# LedTaster_4TE_3_54.net
KiCad netlist of a schematic drawn in EAGLE
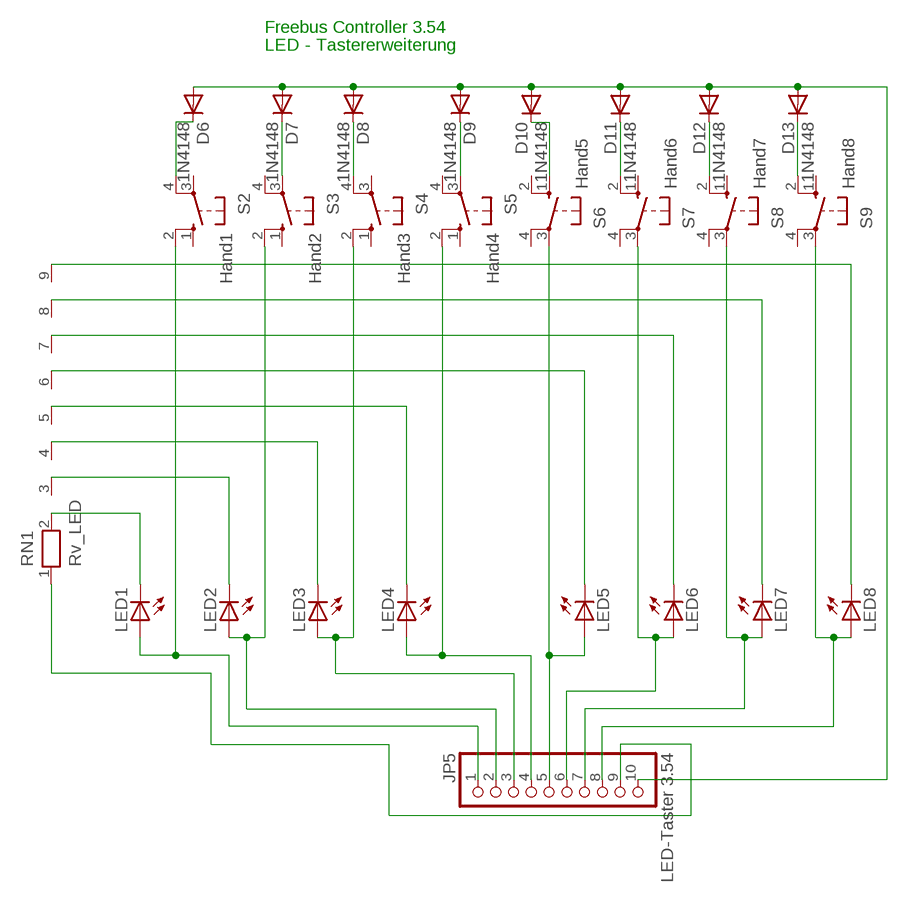
[diagram p0: schematic, sheet 1]

(export (version "E")
  (design (tool "Eeschema 10.0.6"))
  (components
    (comp (ref "D6")
      (value "1N4148")
      (footprint "eagle-import:DO35-10")
      (libsource (lib "eagle-import") (part "1N4148"))
    )
    (comp (ref "D7")
      (value "1N4148")
      (footprint "eagle-import:DO35-10")
      (libsource (lib "eagle-import") (part "1N4148"))
    )
    (comp (ref "D8")
      (value "1N4148")
      (footprint "eagle-import:DO35-10")
      (libsource (lib "eagle-import") (part "1N4148"))
    )
    (comp (ref "D9")
      (value "1N4148")
      (footprint "eagle-import:DO35-10")
      (libsource (lib "eagle-import") (part "1N4148"))
    )
    (comp (ref "D10")
      (value "1N4148")
      (footprint "eagle-import:DO35-10")
      (libsource (lib "eagle-import") (part "1N4148"))
    )
    (comp (ref "D11")
      (value "1N4148")
      (footprint "eagle-import:DO35-10")
      (libsource (lib "eagle-import") (part "1N4148"))
    )
    (comp (ref "D12")
      (value "1N4148")
      (footprint "eagle-import:DO35-10")
      (libsource (lib "eagle-import") (part "1N4148"))
    )
    (comp (ref "D13")
      (value "1N4148")
      (footprint "eagle-import:DO35-10")
      (libsource (lib "eagle-import") (part "1N4148"))
    )
    (comp (ref "JP5")
      (value "LED-Taster 3.54")
      (footprint "eagle-import:1X10")
      (libsource (lib "eagle-import") (part "PINHD-1X10"))
    )
    (comp (ref "LED1")
      (value "LED3MM")
      (footprint "eagle-import:LED3MM")
      (libsource (lib "eagle-import") (part "LED3MM"))
    )
    (comp (ref "LED2")
      (value "LED3MM")
      (footprint "eagle-import:LED3MM")
      (libsource (lib "eagle-import") (part "LED3MM"))
    )
    (comp (ref "LED3")
      (value "LED3MM")
      (footprint "eagle-import:LED3MM")
      (libsource (lib "eagle-import") (part "LED3MM"))
    )
    (comp (ref "LED4")
      (value "LED3MM")
      (footprint "eagle-import:LED3MM")
      (libsource (lib "eagle-import") (part "LED3MM"))
    )
    (comp (ref "LED5")
      (value "LED3MM")
      (footprint "eagle-import:LED3MM")
      (libsource (lib "eagle-import") (part "LED3MM"))
    )
    (comp (ref "LED6")
      (value "LED3MM")
      (footprint "eagle-import:LED3MM")
      (libsource (lib "eagle-import") (part "LED3MM"))
    )
    (comp (ref "LED7")
      (value "LED3MM")
      (footprint "eagle-import:LED3MM")
      (libsource (lib "eagle-import") (part "LED3MM"))
    )
    (comp (ref "LED8")
      (value "LED3MM")
      (footprint "eagle-import:LED3MM")
      (libsource (lib "eagle-import") (part "LED3MM"))
    )
    (comp (ref "RN1")
      (value "Rv_LED")
      (footprint "eagle-import:RN-9")
      (libsource (lib "eagle-import") (part "RN08"))
    )
    (comp (ref "S2")
      (value "Hand1")
      (footprint "eagle-import:B3F-10XX")
      (libsource (lib "eagle-import") (part "10-XX"))
    )
    (comp (ref "S3")
      (value "Hand2")
      (footprint "eagle-import:B3F-10XX")
      (libsource (lib "eagle-import") (part "10-XX"))
    )
    (comp (ref "S4")
      (value "Hand3")
      (footprint "eagle-import:B3F-10XX")
      (libsource (lib "eagle-import") (part "10-XX"))
    )
    (comp (ref "S5")
      (value "Hand4")
      (footprint "eagle-import:B3F-10XX")
      (libsource (lib "eagle-import") (part "10-XX"))
    )
    (comp (ref "S6")
      (value "Hand5")
      (footprint "eagle-import:B3F-10XX")
      (libsource (lib "eagle-import") (part "10-XX"))
    )
    (comp (ref "S7")
      (value "Hand6")
      (footprint "eagle-import:B3F-10XX")
      (libsource (lib "eagle-import") (part "10-XX"))
    )
    (comp (ref "S8")
      (value "Hand7")
      (footprint "eagle-import:B3F-10XX")
      (libsource (lib "eagle-import") (part "10-XX"))
    )
    (comp (ref "S9")
      (value "Hand8")
      (footprint "eagle-import:B3F-10XX")
      (libsource (lib "eagle-import") (part "10-XX"))
    )
  )
  (nets
    (net (code "1") (name "Net-(D10-PadA)") (class "Default")
      (node (ref "D10") (pin "A") (pinfunction "A_A") (pintype "passive"))
      (node (ref "D11") (pin "A") (pinfunction "A_A") (pintype "passive"))
      (node (ref "D12") (pin "A") (pinfunction "A_A") (pintype "passive"))
      (node (ref "D13") (pin "A") (pinfunction "A_A") (pintype "passive"))
      (node (ref "D6") (pin "A") (pinfunction "A_A") (pintype "passive"))
      (node (ref "D7") (pin "A") (pinfunction "A_A") (pintype "passive"))
      (node (ref "D8") (pin "A") (pinfunction "A_A") (pintype "passive"))
      (node (ref "D9") (pin "A") (pinfunction "A_A") (pintype "passive"))
      (node (ref "JP5") (pin "10") (pinfunction "10_10") (pintype "passive"))
    )
    (net (code "2") (name "Net-(JP5-Pad9)") (class "Default")
      (node (ref "JP5") (pin "9") (pinfunction "9_9") (pintype "passive"))
      (node (ref "RN1") (pin "1") (pinfunction "1_1") (pintype "passive"))
    )
    (net (code "3") (name "Net-(LED1-C)") (class "Default")
      (node (ref "LED1") (pin "K") (pinfunction "C_K") (pintype "passive"))
      (node (ref "RN1") (pin "2") (pinfunction "2_2") (pintype "passive"))
    )
    (net (code "4") (name "Net-(LED2-C)") (class "Default")
      (node (ref "LED2") (pin "K") (pinfunction "C_K") (pintype "passive"))
      (node (ref "RN1") (pin "3") (pinfunction "3_3") (pintype "passive"))
    )
    (net (code "5") (name "Net-(LED3-C)") (class "Default")
      (node (ref "LED3") (pin "K") (pinfunction "C_K") (pintype "passive"))
      (node (ref "RN1") (pin "4") (pinfunction "4_4") (pintype "passive"))
    )
    (net (code "6") (name "Net-(LED4-C)") (class "Default")
      (node (ref "LED4") (pin "K") (pinfunction "C_K") (pintype "passive"))
      (node (ref "RN1") (pin "5") (pinfunction "5_5") (pintype "passive"))
    )
    (net (code "7") (name "Net-(LED5-C)") (class "Default")
      (node (ref "LED5") (pin "K") (pinfunction "C_K") (pintype "passive"))
      (node (ref "RN1") (pin "6") (pinfunction "6_6") (pintype "passive"))
    )
    (net (code "8") (name "Net-(LED6-C)") (class "Default")
      (node (ref "LED6") (pin "K") (pinfunction "C_K") (pintype "passive"))
      (node (ref "RN1") (pin "7") (pinfunction "7_7") (pintype "passive"))
    )
    (net (code "9") (name "Net-(LED7-C)") (class "Default")
      (node (ref "LED7") (pin "K") (pinfunction "C_K") (pintype "passive"))
      (node (ref "RN1") (pin "8") (pinfunction "8_8") (pintype "passive"))
    )
    (net (code "10") (name "Net-(LED8-C)") (class "Default")
      (node (ref "LED8") (pin "K") (pinfunction "C_K") (pintype "passive"))
      (node (ref "RN1") (pin "9") (pinfunction "9_9") (pintype "passive"))
    )
    (net (code "11") (name "Net-(S2-P1)") (class "Default")
      (node (ref "D6") (pin "C") (pinfunction "C_C") (pintype "passive"))
      (node (ref "S2") (pin "4") (pinfunction "P1_4") (pintype "passive"))
    )
    (net (code "12") (name "Net-(S2-S1)") (class "Default")
      (node (ref "JP5") (pin "1") (pinfunction "1_1") (pintype "passive"))
      (node (ref "LED1") (pin "A") (pinfunction "A_A") (pintype "passive"))
      (node (ref "S2") (pin "2") (pinfunction "S1_2") (pintype "passive"))
    )
    (net (code "13") (name "Net-(S3-P)") (class "Default")
      (node (ref "D7") (pin "C") (pinfunction "C_C") (pintype "passive"))
      (node (ref "S3") (pin "3") (pinfunction "P_3") (pintype "passive"))
    )
    (net (code "14") (name "Net-(S3-S1)") (class "Default")
      (node (ref "JP5") (pin "2") (pinfunction "2_2") (pintype "passive"))
      (node (ref "LED2") (pin "A") (pinfunction "A_A") (pintype "passive"))
      (node (ref "S3") (pin "2") (pinfunction "S1_2") (pintype "passive"))
    )
    (net (code "15") (name "Net-(S4-P1)") (class "Default")
      (node (ref "D8") (pin "C") (pinfunction "C_C") (pintype "passive"))
      (node (ref "S4") (pin "4") (pinfunction "P1_4") (pintype "passive"))
    )
    (net (code "16") (name "Net-(S4-S1)") (class "Default")
      (node (ref "JP5") (pin "3") (pinfunction "3_3") (pintype "passive"))
      (node (ref "LED3") (pin "A") (pinfunction "A_A") (pintype "passive"))
      (node (ref "S4") (pin "2") (pinfunction "S1_2") (pintype "passive"))
    )
    (net (code "17") (name "Net-(S5-P)") (class "Default")
      (node (ref "D9") (pin "C") (pinfunction "C_C") (pintype "passive"))
      (node (ref "S5") (pin "3") (pinfunction "P_3") (pintype "passive"))
    )
    (net (code "18") (name "Net-(S5-S1)") (class "Default")
      (node (ref "JP5") (pin "4") (pinfunction "4_4") (pintype "passive"))
      (node (ref "LED4") (pin "A") (pinfunction "A_A") (pintype "passive"))
      (node (ref "S5") (pin "2") (pinfunction "S1_2") (pintype "passive"))
    )
    (net (code "19") (name "Net-(S6-P)") (class "Default")
      (node (ref "JP5") (pin "5") (pinfunction "5_5") (pintype "passive"))
      (node (ref "LED5") (pin "A") (pinfunction "A_A") (pintype "passive"))
      (node (ref "S6") (pin "3") (pinfunction "P_3") (pintype "passive"))
    )
    (net (code "20") (name "Net-(S6-S)") (class "Default")
      (node (ref "D10") (pin "C") (pinfunction "C_C") (pintype "passive"))
      (node (ref "S6") (pin "1") (pinfunction "S_1") (pintype "passive"))
    )
    (net (code "21") (name "Net-(S7-P)") (class "Default")
      (node (ref "JP5") (pin "6") (pinfunction "6_6") (pintype "passive"))
      (node (ref "LED6") (pin "A") (pinfunction "A_A") (pintype "passive"))
      (node (ref "S7") (pin "3") (pinfunction "P_3") (pintype "passive"))
    )
    (net (code "22") (name "Net-(S7-S1)") (class "Default")
      (node (ref "D11") (pin "C") (pinfunction "C_C") (pintype "passive"))
      (node (ref "S7") (pin "2") (pinfunction "S1_2") (pintype "passive"))
    )
    (net (code "23") (name "Net-(S8-P)") (class "Default")
      (node (ref "JP5") (pin "7") (pinfunction "7_7") (pintype "passive"))
      (node (ref "LED7") (pin "A") (pinfunction "A_A") (pintype "passive"))
      (node (ref "S8") (pin "3") (pinfunction "P_3") (pintype "passive"))
    )
    (net (code "24") (name "Net-(S8-S1)") (class "Default")
      (node (ref "D12") (pin "C") (pinfunction "C_C") (pintype "passive"))
      (node (ref "S8") (pin "2") (pinfunction "S1_2") (pintype "passive"))
    )
    (net (code "25") (name "Net-(S9-P)") (class "Default")
      (node (ref "JP5") (pin "8") (pinfunction "8_8") (pintype "passive"))
      (node (ref "LED8") (pin "A") (pinfunction "A_A") (pintype "passive"))
      (node (ref "S9") (pin "3") (pinfunction "P_3") (pintype "passive"))
    )
    (net (code "26") (name "Net-(S9-S1)") (class "Default")
      (node (ref "D13") (pin "C") (pinfunction "C_C") (pintype "passive"))
      (node (ref "S9") (pin "2") (pinfunction "S1_2") (pintype "passive"))
    )
    (net (code "27") (name "unconnected-(S2-P-Pad3)") (class "Default")
      (node (ref "S2") (pin "3") (pinfunction "P_3") (pintype "passive"))
    )
    (net (code "28") (name "unconnected-(S2-S-Pad1)") (class "Default")
      (node (ref "S2") (pin "1") (pinfunction "S_1") (pintype "passive"))
    )
    (net (code "29") (name "unconnected-(S3-P1-Pad4)") (class "Default")
      (node (ref "S3") (pin "4") (pinfunction "P1_4") (pintype "passive"))
    )
    (net (code "30") (name "unconnected-(S3-S-Pad1)") (class "Default")
      (node (ref "S3") (pin "1") (pinfunction "S_1") (pintype "passive"))
    )
    (net (code "31") (name "unconnected-(S4-P-Pad3)") (class "Default")
      (node (ref "S4") (pin "3") (pinfunction "P_3") (pintype "passive"))
    )
    (net (code "32") (name "unconnected-(S4-S-Pad1)") (class "Default")
      (node (ref "S4") (pin "1") (pinfunction "S_1") (pintype "passive"))
    )
    (net (code "33") (name "unconnected-(S5-P1-Pad4)") (class "Default")
      (node (ref "S5") (pin "4") (pinfunction "P1_4") (pintype "passive"))
    )
    (net (code "34") (name "unconnected-(S5-S-Pad1)") (class "Default")
      (node (ref "S5") (pin "1") (pinfunction "S_1") (pintype "passive"))
    )
    (net (code "35") (name "unconnected-(S6-P1-Pad4)") (class "Default")
      (node (ref "S6") (pin "4") (pinfunction "P1_4") (pintype "passive"))
    )
    (net (code "36") (name "unconnected-(S6-S1-Pad2)") (class "Default")
      (node (ref "S6") (pin "2") (pinfunction "S1_2") (pintype "passive"))
    )
    (net (code "37") (name "unconnected-(S7-P1-Pad4)") (class "Default")
      (node (ref "S7") (pin "4") (pinfunction "P1_4") (pintype "passive"))
    )
    (net (code "38") (name "unconnected-(S7-S-Pad1)") (class "Default")
      (node (ref "S7") (pin "1") (pinfunction "S_1") (pintype "passive"))
    )
    (net (code "39") (name "unconnected-(S8-P1-Pad4)") (class "Default")
      (node (ref "S8") (pin "4") (pinfunction "P1_4") (pintype "passive"))
    )
    (net (code "40") (name "unconnected-(S8-S-Pad1)") (class "Default")
      (node (ref "S8") (pin "1") (pinfunction "S_1") (pintype "passive"))
    )
    (net (code "41") (name "unconnected-(S9-P1-Pad4)") (class "Default")
      (node (ref "S9") (pin "4") (pinfunction "P1_4") (pintype "passive"))
    )
    (net (code "42") (name "unconnected-(S9-S-Pad1)") (class "Default")
      (node (ref "S9") (pin "1") (pinfunction "S_1") (pintype "passive"))
    )
  )
)
